# ADXL345.net
KiCad netlist of a schematic drawn in Altium Designer
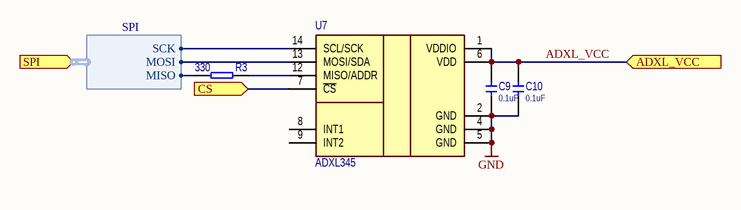
[diagram p0: ADXL345.SchDoc]

(export (version "E")
  (design (tool "Eeschema 10.0.6"))
  (components
    (comp (ref "C9")
      (value "0.1uF")
      (footprint "CERCAP 0402")
      (description "Capacitor")
      (fields (field (name "Comment") "CERCAP 0402 0.1uF * X7R"))
      (libsource (lib "!main") (part "!Capacitor"))
    )
    (comp (ref "C10")
      (value "0.1uF")
      (footprint "CERCAP 0402")
      (description "Capacitor")
      (fields (field (name "Comment") "CERCAP 0402 0.1uF * X7R"))
      (libsource (lib "!main") (part "!Capacitor"))
    )
    (comp (ref "R3")
      (value "330")
      (footprint "RES 0402")
      (description "Resistor")
      (fields (field (name "Comment") "RES 0402 330"))
      (libsource (lib "!main") (part "!Resistor"))
    )
    (comp (ref "U7")
      (value "ADXL345")
      (footprint "LGA14_ADXL345")
      (description "Acc")
      (libsource (lib "sensors") (part "ADXL345"))
    )
  )
  (nets
    (net (code "2") (name "/ADXL_VCC") (class "Default")
      (node (ref "C10") (pin "2") (pintype "passive"))
      (node (ref "C9") (pin "2") (pintype "passive"))
      (node (ref "U7") (pin "1") (pinfunction "VDDIO_1") (pintype "passive"))
      (node (ref "U7") (pin "6") (pinfunction "VDD_6") (pintype "passive"))
    )
    (net (code "3") (name "/CS") (class "Default")
      (node (ref "U7") (pin "7") (pinfunction "~{CS}_7") (pintype "passive"))
    )
    (net (code "4") (name "/MISO") (class "Default")
      (node (ref "R3") (pin "1") (pinfunction "11_1") (pintype "passive"))
    )
    (net (code "5") (name "/MOSI") (class "Default")
      (node (ref "U7") (pin "13") (pinfunction "MOSI/SDA_13") (pintype "passive"))
    )
    (net (code "6") (name "/SCK") (class "Default")
      (node (ref "U7") (pin "14") (pinfunction "SCL/SCK_14") (pintype "passive"))
    )
    (net (code "8") (name "GND") (class "Default")
      (node (ref "C10") (pin "1") (pintype "passive"))
      (node (ref "C9") (pin "1") (pintype "passive"))
      (node (ref "U7") (pin "2") (pinfunction "GND_2") (pintype "passive"))
      (node (ref "U7") (pin "4") (pinfunction "GND_4") (pintype "passive"))
      (node (ref "U7") (pin "5") (pinfunction "GND_5") (pintype "passive"))
    )
    (net (code "9") (name "Net-(R3-12)") (class "Default")
      (node (ref "R3") (pin "2") (pinfunction "12_2") (pintype "passive"))
      (node (ref "U7") (pin "12") (pinfunction "MISO/ADDR_12") (pintype "passive"))
    )
    (net (code "10") (name "unconnected-(U7-INT1-Pad8)") (class "Default")
      (node (ref "U7") (pin "8") (pinfunction "INT1_8") (pintype "passive"))
    )
    (net (code "11") (name "unconnected-(U7-INT2-Pad9)") (class "Default")
      (node (ref "U7") (pin "9") (pinfunction "INT2_9") (pintype "passive"))
    )
  )
)
